# cinamin.net
KiCad netlist of a schematic drawn in EAGLE
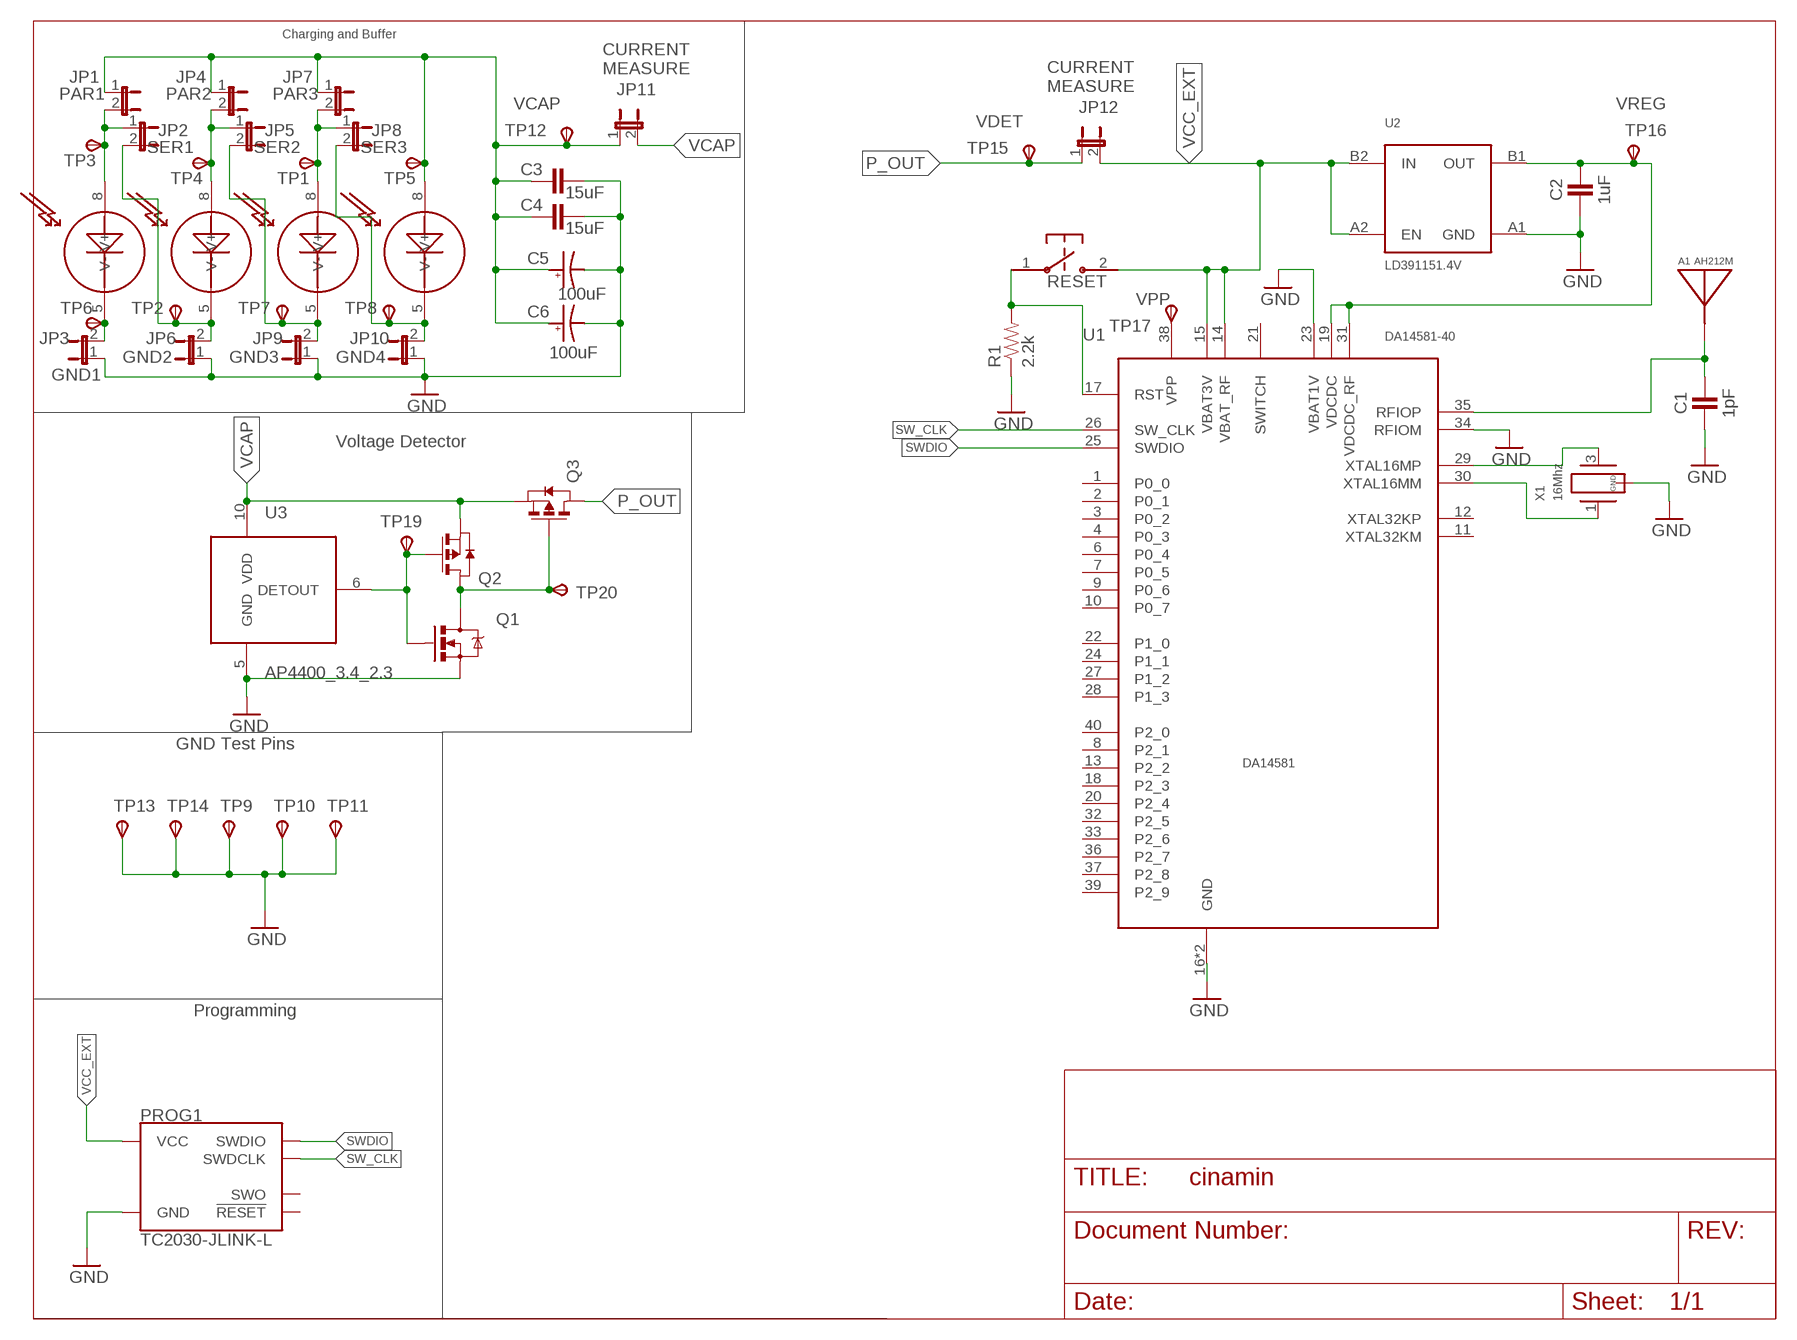
[diagram p0: schematic, sheet 1]

(export (version "E")
  (design (tool "Eeschema 10.0.6"))
  (components
    (comp (ref "A1")
      (value "AH212M")
      (footprint "eagle-import:AH212M")
      (libsource (lib "eagle-import") (part "AH212M"))
    )
    (comp (ref "C1")
      (value "1pF")
      (footprint "eagle-import:0402_CAP")
      (libsource (lib "eagle-import") (part "CAPACITOR"))
    )
    (comp (ref "C2")
      (value "1uF")
      (footprint "eagle-import:0402_CAP")
      (libsource (lib "eagle-import") (part "CAPACITOR"))
    )
    (comp (ref "C3")
      (value "15uF")
      (footprint "eagle-import:0402_CAP")
      (libsource (lib "eagle-import") (part "CAPACITOR"))
    )
    (comp (ref "C4")
      (value "15uF")
      (footprint "eagle-import:0402_CAP")
      (libsource (lib "eagle-import") (part "CAPACITOR"))
    )
    (comp (ref "C5")
      (value "100uF")
      (footprint "eagle-import:CAP0603")
      (libsource (lib "eagle-import") (part "CAP_POL0603"))
    )
    (comp (ref "C6")
      (value "100uF")
      (footprint "eagle-import:CAP0603")
      (libsource (lib "eagle-import") (part "CAP_POL0603"))
    )
    (comp (ref "D1")
      (value "CPC1822")
      (footprint "eagle-import:SOIC-8")
      (libsource (lib "eagle-import") (part "CPC1822"))
    )
    (comp (ref "D2")
      (value "CPC1822")
      (footprint "eagle-import:SOIC-8")
      (libsource (lib "eagle-import") (part "CPC1822"))
    )
    (comp (ref "D3")
      (value "CPC1822")
      (footprint "eagle-import:SOIC-8")
      (libsource (lib "eagle-import") (part "CPC1822"))
    )
    (comp (ref "D4")
      (value "CPC1822")
      (footprint "eagle-import:SOIC-8")
      (libsource (lib "eagle-import") (part "CPC1822"))
    )
    (comp (ref "JP1")
      (value "PAR1")
      (footprint "eagle-import:1X02")
      (libsource (lib "eagle-import") (part "JUMPER-2PTH"))
    )
    (comp (ref "JP2")
      (value "SER1")
      (footprint "eagle-import:1X02")
      (libsource (lib "eagle-import") (part "JUMPER-2PTH"))
    )
    (comp (ref "JP3")
      (value "GND1")
      (footprint "eagle-import:1X02")
      (libsource (lib "eagle-import") (part "JUMPER-2PTH"))
    )
    (comp (ref "JP4")
      (value "PAR2")
      (footprint "eagle-import:1X02")
      (libsource (lib "eagle-import") (part "JUMPER-2PTH"))
    )
    (comp (ref "JP5")
      (value "SER2")
      (footprint "eagle-import:1X02")
      (libsource (lib "eagle-import") (part "JUMPER-2PTH"))
    )
    (comp (ref "JP6")
      (value "GND2")
      (footprint "eagle-import:1X02")
      (libsource (lib "eagle-import") (part "JUMPER-2PTH"))
    )
    (comp (ref "JP7")
      (value "PAR3")
      (footprint "eagle-import:1X02")
      (libsource (lib "eagle-import") (part "JUMPER-2PTH"))
    )
    (comp (ref "JP8")
      (value "SER3")
      (footprint "eagle-import:1X02")
      (libsource (lib "eagle-import") (part "JUMPER-2PTH"))
    )
    (comp (ref "JP9")
      (value "GND3")
      (footprint "eagle-import:1X02")
      (libsource (lib "eagle-import") (part "JUMPER-2PTH"))
    )
    (comp (ref "JP10")
      (value "GND4")
      (footprint "eagle-import:1X02")
      (libsource (lib "eagle-import") (part "JUMPER-2PTH"))
    )
    (comp (ref "JP11")
      (value "CURRENT_MEASURE1")
      (footprint "eagle-import:1X02")
      (libsource (lib "eagle-import") (part "JUMPER-2PTH"))
    )
    (comp (ref "JP12")
      (value "CURRENT_MEASURE2")
      (footprint "eagle-import:1X02")
      (libsource (lib "eagle-import") (part "JUMPER-2PTH"))
    )
    (comp (ref "PROG1")
      (value "TC2030-JLINK-L")
      (footprint "eagle-import:TC2030-IDC")
      (libsource (lib "eagle-import") (part "TC2030-JLINK-L"))
    )
    (comp (ref "Q1")
      (value "MOSFET-NCHANNELXFDN-3")
      (footprint "eagle-import:XFDFN-3")
      (libsource (lib "eagle-import") (part "MOSFET-NCHANNELXFDN-3"))
    )
    (comp (ref "Q2")
      (value "MOSFET-PCHANNEL")
      (footprint "eagle-import:XFDFN-3")
      (libsource (lib "eagle-import") (part "MOSFET-PCHANNEL"))
    )
    (comp (ref "Q3")
      (value "MOSFET-PCHANNEL")
      (footprint "eagle-import:XFDFN-3")
      (libsource (lib "eagle-import") (part "MOSFET-PCHANNEL"))
    )
    (comp (ref "R1")
      (value "2.2k")
      (footprint "eagle-import:0402_RES")
      (libsource (lib "eagle-import") (part "RESISTOR0402_RES"))
    )
    (comp (ref "RESET")
      (value "B3U-1000P")
      (footprint "eagle-import:B3U-1000P")
      (libsource (lib "eagle-import") (part "B3U-1000P"))
    )
    (comp (ref "TP1")
      (value "D3H")
      (footprint "eagle-import:P1-13")
      (libsource (lib "eagle-import") (part "TPSPAD1-13"))
    )
    (comp (ref "TP2")
      (value "D2L")
      (footprint "eagle-import:P1-13")
      (libsource (lib "eagle-import") (part "TPSPAD1-13"))
    )
    (comp (ref "TP3")
      (value "D1H")
      (footprint "eagle-import:P1-13")
      (libsource (lib "eagle-import") (part "TPSPAD1-13"))
    )
    (comp (ref "TP4")
      (value "D2H")
      (footprint "eagle-import:P1-13")
      (libsource (lib "eagle-import") (part "TPSPAD1-13"))
    )
    (comp (ref "TP5")
      (value "D4H")
      (footprint "eagle-import:P1-13")
      (libsource (lib "eagle-import") (part "TPSPAD1-13"))
    )
    (comp (ref "TP6")
      (value "D1L")
      (footprint "eagle-import:P1-13")
      (libsource (lib "eagle-import") (part "TPSPAD1-13"))
    )
    (comp (ref "TP7")
      (value "D3L")
      (footprint "eagle-import:P1-13")
      (libsource (lib "eagle-import") (part "TPSPAD1-13"))
    )
    (comp (ref "TP8")
      (value "D4L")
      (footprint "eagle-import:P1-13")
      (libsource (lib "eagle-import") (part "TPSPAD1-13"))
    )
    (comp (ref "TP9")
      (value "GND")
      (footprint "eagle-import:P1-13")
      (libsource (lib "eagle-import") (part "TPSPAD1-13"))
    )
    (comp (ref "TP10")
      (value "GND")
      (footprint "eagle-import:P1-13")
      (libsource (lib "eagle-import") (part "TPSPAD1-13"))
    )
    (comp (ref "TP11")
      (value "GND")
      (footprint "eagle-import:P1-13")
      (libsource (lib "eagle-import") (part "TPSPAD1-13"))
    )
    (comp (ref "TP12")
      (value "VCAP")
      (footprint "eagle-import:P1-13")
      (libsource (lib "eagle-import") (part "TPSPAD1-13"))
    )
    (comp (ref "TP13")
      (value "GND")
      (footprint "eagle-import:P1-13")
      (libsource (lib "eagle-import") (part "TPSPAD1-13"))
    )
    (comp (ref "TP14")
      (value "GND")
      (footprint "eagle-import:P1-13")
      (libsource (lib "eagle-import") (part "TPSPAD1-13"))
    )
    (comp (ref "TP15")
      (value "VDET")
      (footprint "eagle-import:P1-13")
      (libsource (lib "eagle-import") (part "TPSPAD1-13"))
    )
    (comp (ref "TP16")
      (value "VREG")
      (footprint "eagle-import:P1-13")
      (libsource (lib "eagle-import") (part "TPSPAD1-13"))
    )
    (comp (ref "TP17")
      (value "VPP")
      (footprint "eagle-import:P1-13")
      (libsource (lib "eagle-import") (part "TPSPAD1-13"))
    )
    (comp (ref "TP19")
      (value "VCAP")
      (footprint "eagle-import:P1-13")
      (libsource (lib "eagle-import") (part "TPSPAD1-13"))
    )
    (comp (ref "TP20")
      (value "VCAP")
      (footprint "eagle-import:P1-13")
      (libsource (lib "eagle-import") (part "TPSPAD1-13"))
    )
    (comp (ref "U1")
      (value "DA14581-40")
      (footprint "eagle-import:QFN-40-5MM")
      (libsource (lib "eagle-import") (part "DA14581-40"))
    )
    (comp (ref "U2")
      (value "LD391151.4V")
      (footprint "eagle-import:FLIP_CHIP-4")
      (libsource (lib "eagle-import") (part "LD391151.4V"))
    )
    (comp (ref "U3")
      (value "AP4400_3.4_2.3")
      (footprint "eagle-import:TSOP-10")
      (libsource (lib "eagle-import") (part "AP4400"))
    )
    (comp (ref "X1")
      (value "16Mhz")
      (footprint "eagle-import:TXC-8Y")
      (libsource (lib "eagle-import") (part "TXC-8Y"))
    )
  )
  (nets
    (net (code "1") (name "GND") (class "Default")
      (node (ref "C1") (pin "2") (pinfunction "2_2") (pintype "bidirectional"))
      (node (ref "C2") (pin "2") (pinfunction "2_2") (pintype "bidirectional"))
      (node (ref "C3") (pin "2") (pinfunction "2_2") (pintype "bidirectional"))
      (node (ref "C4") (pin "2") (pinfunction "2_2") (pintype "bidirectional"))
      (node (ref "C5") (pin "NEG") (pinfunction "ANODE_NEG") (pintype "bidirectional"))
      (node (ref "C6") (pin "NEG") (pinfunction "ANODE_NEG") (pintype "bidirectional"))
      (node (ref "JP10") (pin "1") (pinfunction "1_1") (pintype "passive"))
      (node (ref "JP3") (pin "1") (pinfunction "1_1") (pintype "passive"))
      (node (ref "JP6") (pin "1") (pinfunction "1_1") (pintype "passive"))
      (node (ref "JP9") (pin "1") (pinfunction "1_1") (pintype "passive"))
      (node (ref "PROG1") (pin "5") (pinfunction "GND_5") (pintype "bidirectional"))
      (node (ref "Q1") (pin "S") (pinfunction "S_S") (pintype "passive"))
      (node (ref "R1") (pin "1") (pinfunction "1_1") (pintype "passive"))
      (node (ref "TP10") (pin "TP") (pinfunction "PP_TP") (pintype "input"))
      (node (ref "TP11") (pin "TP") (pinfunction "PP_TP") (pintype "input"))
      (node (ref "TP13") (pin "TP") (pinfunction "PP_TP") (pintype "input"))
      (node (ref "TP14") (pin "TP") (pinfunction "PP_TP") (pintype "input"))
      (node (ref "TP9") (pin "TP") (pinfunction "PP_TP") (pintype "input"))
      (node (ref "U1") (pin "16") (pinfunction "GND_16") (pintype "bidirectional"))
      (node (ref "U1") (pin "23") (pinfunction "VBAT1V_23") (pintype "bidirectional"))
      (node (ref "U1") (pin "34") (pinfunction "RFIOM_34") (pintype "bidirectional"))
      (node (ref "U1") (pin "PAD") (pinfunction "GND_PAD") (pintype "bidirectional"))
      (node (ref "U2") (pin "A1") (pinfunction "GND_A1") (pintype "bidirectional"))
      (node (ref "U3") (pin "5") (pinfunction "GND_5") (pintype "bidirectional"))
      (node (ref "X1") (pin "2") (pinfunction "GND_2") (pintype "bidirectional"))
      (node (ref "X1") (pin "4") (pinfunction "GND_4") (pintype "bidirectional"))
    )
    (net (code "2") (name "Net-(A1-ANTENNA)") (class "Default")
      (node (ref "A1") (pin "P1") (pinfunction "ANTENNA_P1") (pintype "bidirectional"))
      (node (ref "C1") (pin "1") (pinfunction "1_1") (pintype "bidirectional"))
      (node (ref "U1") (pin "35") (pinfunction "RFIOP_35") (pintype "bidirectional"))
    )
    (net (code "3") (name "Net-(C5-CATHODE)") (class "Default")
      (node (ref "C3") (pin "1") (pinfunction "1_1") (pintype "bidirectional"))
      (node (ref "C4") (pin "1") (pinfunction "1_1") (pintype "bidirectional"))
      (node (ref "C5") (pin "POS") (pinfunction "CATHODE_POS") (pintype "bidirectional"))
      (node (ref "C6") (pin "POS") (pinfunction "CATHODE_POS") (pintype "bidirectional"))
      (node (ref "D4") (pin "8") (pinfunction "V+_8") (pintype "bidirectional"))
      (node (ref "JP1") (pin "1") (pinfunction "1_1") (pintype "passive"))
      (node (ref "JP11") (pin "1") (pinfunction "1_1") (pintype "passive"))
      (node (ref "JP4") (pin "1") (pinfunction "1_1") (pintype "passive"))
      (node (ref "JP7") (pin "1") (pinfunction "1_1") (pintype "passive"))
      (node (ref "TP12") (pin "TP") (pinfunction "PP_TP") (pintype "input"))
      (node (ref "TP5") (pin "TP") (pinfunction "PP_TP") (pintype "input"))
    )
    (net (code "4") (name "Net-(D1-V+)") (class "Default")
      (node (ref "D1") (pin "8") (pinfunction "V+_8") (pintype "bidirectional"))
      (node (ref "JP1") (pin "2") (pinfunction "2_2") (pintype "passive"))
      (node (ref "JP2") (pin "1") (pinfunction "1_1") (pintype "passive"))
      (node (ref "TP3") (pin "TP") (pinfunction "PP_TP") (pintype "input"))
    )
    (net (code "5") (name "Net-(D1-V-)") (class "Default")
      (node (ref "D1") (pin "5") (pinfunction "V-_5") (pintype "bidirectional"))
      (node (ref "JP3") (pin "2") (pinfunction "2_2") (pintype "passive"))
      (node (ref "TP6") (pin "TP") (pinfunction "PP_TP") (pintype "input"))
    )
    (net (code "6") (name "Net-(D2-V+)") (class "Default")
      (node (ref "D2") (pin "8") (pinfunction "V+_8") (pintype "bidirectional"))
      (node (ref "JP4") (pin "2") (pinfunction "2_2") (pintype "passive"))
      (node (ref "JP5") (pin "1") (pinfunction "1_1") (pintype "passive"))
      (node (ref "TP4") (pin "TP") (pinfunction "PP_TP") (pintype "input"))
    )
    (net (code "7") (name "Net-(D2-V-)") (class "Default")
      (node (ref "D2") (pin "5") (pinfunction "V-_5") (pintype "bidirectional"))
      (node (ref "JP2") (pin "2") (pinfunction "2_2") (pintype "passive"))
      (node (ref "JP6") (pin "2") (pinfunction "2_2") (pintype "passive"))
      (node (ref "TP2") (pin "TP") (pinfunction "PP_TP") (pintype "input"))
    )
    (net (code "8") (name "Net-(D3-V+)") (class "Default")
      (node (ref "D3") (pin "8") (pinfunction "V+_8") (pintype "bidirectional"))
      (node (ref "JP7") (pin "2") (pinfunction "2_2") (pintype "passive"))
      (node (ref "JP8") (pin "1") (pinfunction "1_1") (pintype "passive"))
      (node (ref "TP1") (pin "TP") (pinfunction "PP_TP") (pintype "input"))
    )
    (net (code "9") (name "Net-(D3-V-)") (class "Default")
      (node (ref "D3") (pin "5") (pinfunction "V-_5") (pintype "bidirectional"))
      (node (ref "JP5") (pin "2") (pinfunction "2_2") (pintype "passive"))
      (node (ref "JP9") (pin "2") (pinfunction "2_2") (pintype "passive"))
      (node (ref "TP7") (pin "TP") (pinfunction "PP_TP") (pintype "input"))
    )
    (net (code "10") (name "Net-(D4-V-)") (class "Default")
      (node (ref "D4") (pin "5") (pinfunction "V-_5") (pintype "bidirectional"))
      (node (ref "JP10") (pin "2") (pinfunction "2_2") (pintype "passive"))
      (node (ref "JP8") (pin "2") (pinfunction "2_2") (pintype "passive"))
      (node (ref "TP8") (pin "TP") (pinfunction "PP_TP") (pintype "input"))
    )
    (net (code "11") (name "Net-(RESET-P$1)") (class "Default")
      (node (ref "R1") (pin "2") (pinfunction "2_2") (pintype "passive"))
      (node (ref "RESET") (pin "1") (pinfunction "P$1_1") (pintype "passive"))
      (node (ref "U1") (pin "17") (pinfunction "RST_17") (pintype "bidirectional"))
    )
    (net (code "12") (name "Net-(TP16-PP)") (class "Default")
      (node (ref "C2") (pin "1") (pinfunction "1_1") (pintype "bidirectional"))
      (node (ref "TP16") (pin "TP") (pinfunction "PP_TP") (pintype "input"))
      (node (ref "U1") (pin "19") (pinfunction "VDCDC_19") (pintype "bidirectional"))
      (node (ref "U1") (pin "31") (pinfunction "VDCDC_RF_31") (pintype "bidirectional"))
      (node (ref "U2") (pin "B1") (pinfunction "OUT_B1") (pintype "bidirectional"))
    )
    (net (code "13") (name "Net-(TP17-PP)") (class "Default")
      (node (ref "TP17") (pin "TP") (pinfunction "PP_TP") (pintype "input"))
      (node (ref "U1") (pin "38") (pinfunction "VPP_38") (pintype "bidirectional"))
    )
    (net (code "14") (name "Net-(TP19-PP)") (class "Default")
      (node (ref "Q1") (pin "G") (pinfunction "G_G") (pintype "passive"))
      (node (ref "Q2") (pin "G") (pinfunction "G_G") (pintype "passive"))
      (node (ref "TP19") (pin "TP") (pinfunction "PP_TP") (pintype "input"))
      (node (ref "U3") (pin "6") (pinfunction "DETOUT_6") (pintype "bidirectional"))
    )
    (net (code "15") (name "Net-(TP20-PP)") (class "Default")
      (node (ref "Q1") (pin "D") (pinfunction "D_D") (pintype "passive"))
      (node (ref "Q2") (pin "D") (pinfunction "D_D") (pintype "passive"))
      (node (ref "Q3") (pin "G") (pinfunction "G_G") (pintype "passive"))
      (node (ref "TP20") (pin "TP") (pinfunction "PP_TP") (pintype "input"))
    )
    (net (code "16") (name "Net-(U1-XTAL16MM)") (class "Default")
      (node (ref "U1") (pin "30") (pinfunction "XTAL16MM_30") (pintype "bidirectional"))
      (node (ref "X1") (pin "1") (pinfunction "1_1") (pintype "bidirectional"))
    )
    (net (code "17") (name "Net-(U1-XTAL16MP)") (class "Default")
      (node (ref "U1") (pin "29") (pinfunction "XTAL16MP_29") (pintype "bidirectional"))
      (node (ref "X1") (pin "3") (pinfunction "2_3") (pintype "bidirectional"))
    )
    (net (code "18") (name "P_OUT") (class "Default")
      (node (ref "JP12") (pin "1") (pinfunction "1_1") (pintype "passive"))
      (node (ref "Q3") (pin "D") (pinfunction "D_D") (pintype "passive"))
      (node (ref "TP15") (pin "TP") (pinfunction "PP_TP") (pintype "input"))
    )
    (net (code "19") (name "SWDIO") (class "Default")
      (node (ref "PROG1") (pin "2") (pinfunction "SWDIO_2") (pintype "bidirectional"))
      (node (ref "U1") (pin "25") (pinfunction "SWDIO_25") (pintype "bidirectional"))
    )
    (net (code "20") (name "SW_CLK") (class "Default")
      (node (ref "PROG1") (pin "4") (pinfunction "SWDCLK_4") (pintype "bidirectional"))
      (node (ref "U1") (pin "26") (pinfunction "SW_CLK_26") (pintype "bidirectional"))
    )
    (net (code "21") (name "VCAP") (class "Default")
      (node (ref "JP11") (pin "2") (pinfunction "2_2") (pintype "passive"))
      (node (ref "Q2") (pin "S") (pinfunction "S_S") (pintype "passive"))
      (node (ref "Q3") (pin "S") (pinfunction "S_S") (pintype "passive"))
      (node (ref "U3") (pin "10") (pinfunction "VDD_10") (pintype "bidirectional"))
    )
    (net (code "22") (name "VCC_EXT") (class "Default")
      (node (ref "JP12") (pin "2") (pinfunction "2_2") (pintype "passive"))
      (node (ref "PROG1") (pin "1") (pinfunction "VCC_1") (pintype "bidirectional"))
      (node (ref "RESET") (pin "2") (pinfunction "P$2_2") (pintype "passive"))
      (node (ref "U1") (pin "14") (pinfunction "VBAT_RF_14") (pintype "bidirectional"))
      (node (ref "U1") (pin "15") (pinfunction "VBAT3V_15") (pintype "bidirectional"))
      (node (ref "U2") (pin "A2") (pinfunction "EN_A2") (pintype "bidirectional"))
      (node (ref "U2") (pin "B2") (pinfunction "IN_B2") (pintype "bidirectional"))
    )
    (net (code "23") (name "unconnected-(PROG1-SWO-Pad6)") (class "Default")
      (node (ref "PROG1") (pin "6") (pinfunction "SWO_6") (pintype "bidirectional"))
    )
    (net (code "24") (name "unconnected-(PROG1-~{RESET}-Pad3)") (class "Default")
      (node (ref "PROG1") (pin "3") (pinfunction "~{RESET}_3") (pintype "bidirectional"))
    )
    (net (code "25") (name "unconnected-(U1-P0_0-Pad1)") (class "Default")
      (node (ref "U1") (pin "1") (pinfunction "P0_0_1") (pintype "bidirectional"))
    )
    (net (code "26") (name "unconnected-(U1-P0_1-Pad2)") (class "Default")
      (node (ref "U1") (pin "2") (pinfunction "P0_1_2") (pintype "bidirectional"))
    )
    (net (code "27") (name "unconnected-(U1-P0_2-Pad3)") (class "Default")
      (node (ref "U1") (pin "3") (pinfunction "P0_2_3") (pintype "bidirectional"))
    )
    (net (code "28") (name "unconnected-(U1-P0_3-Pad4)") (class "Default")
      (node (ref "U1") (pin "4") (pinfunction "P0_3_4") (pintype "bidirectional"))
    )
    (net (code "29") (name "unconnected-(U1-P0_4-Pad6)") (class "Default")
      (node (ref "U1") (pin "6") (pinfunction "P0_4_6") (pintype "bidirectional"))
    )
    (net (code "30") (name "unconnected-(U1-P0_5-Pad7)") (class "Default")
      (node (ref "U1") (pin "7") (pinfunction "P0_5_7") (pintype "bidirectional"))
    )
    (net (code "31") (name "unconnected-(U1-P0_6-Pad9)") (class "Default")
      (node (ref "U1") (pin "9") (pinfunction "P0_6_9") (pintype "bidirectional"))
    )
    (net (code "32") (name "unconnected-(U1-P0_7-Pad10)") (class "Default")
      (node (ref "U1") (pin "10") (pinfunction "P0_7_10") (pintype "bidirectional"))
    )
    (net (code "33") (name "unconnected-(U1-P1_0-Pad22)") (class "Default")
      (node (ref "U1") (pin "22") (pinfunction "P1_0_22") (pintype "bidirectional"))
    )
    (net (code "34") (name "unconnected-(U1-P1_1-Pad24)") (class "Default")
      (node (ref "U1") (pin "24") (pinfunction "P1_1_24") (pintype "bidirectional"))
    )
    (net (code "35") (name "unconnected-(U1-P1_2-Pad27)") (class "Default")
      (node (ref "U1") (pin "27") (pinfunction "P1_2_27") (pintype "bidirectional"))
    )
    (net (code "36") (name "unconnected-(U1-P1_3-Pad28)") (class "Default")
      (node (ref "U1") (pin "28") (pinfunction "P1_3_28") (pintype "bidirectional"))
    )
    (net (code "37") (name "unconnected-(U1-P2_0-Pad40)") (class "Default")
      (node (ref "U1") (pin "40") (pinfunction "P2_0_40") (pintype "bidirectional"))
    )
    (net (code "38") (name "unconnected-(U1-P2_1-Pad8)") (class "Default")
      (node (ref "U1") (pin "8") (pinfunction "P2_1_8") (pintype "bidirectional"))
    )
    (net (code "39") (name "unconnected-(U1-P2_2-Pad13)") (class "Default")
      (node (ref "U1") (pin "13") (pinfunction "P2_2_13") (pintype "bidirectional"))
    )
    (net (code "40") (name "unconnected-(U1-P2_3-Pad18)") (class "Default")
      (node (ref "U1") (pin "18") (pinfunction "P2_3_18") (pintype "bidirectional"))
    )
    (net (code "41") (name "unconnected-(U1-P2_4-Pad20)") (class "Default")
      (node (ref "U1") (pin "20") (pinfunction "P2_4_20") (pintype "bidirectional"))
    )
    (net (code "42") (name "unconnected-(U1-P2_5-Pad32)") (class "Default")
      (node (ref "U1") (pin "32") (pinfunction "P2_5_32") (pintype "bidirectional"))
    )
    (net (code "43") (name "unconnected-(U1-P2_6-Pad33)") (class "Default")
      (node (ref "U1") (pin "33") (pinfunction "P2_6_33") (pintype "bidirectional"))
    )
    (net (code "44") (name "unconnected-(U1-P2_7-Pad36)") (class "Default")
      (node (ref "U1") (pin "36") (pinfunction "P2_7_36") (pintype "bidirectional"))
    )
    (net (code "45") (name "unconnected-(U1-P2_8-Pad37)") (class "Default")
      (node (ref "U1") (pin "37") (pinfunction "P2_8_37") (pintype "bidirectional"))
    )
    (net (code "46") (name "unconnected-(U1-P2_9-Pad39)") (class "Default")
      (node (ref "U1") (pin "39") (pinfunction "P2_9_39") (pintype "bidirectional"))
    )
    (net (code "47") (name "unconnected-(U1-SWITCH-Pad21)") (class "Default")
      (node (ref "U1") (pin "21") (pinfunction "SWITCH_21") (pintype "bidirectional"))
    )
    (net (code "48") (name "unconnected-(U1-XTAL32KM-Pad11)") (class "Default")
      (node (ref "U1") (pin "11") (pinfunction "XTAL32KM_11") (pintype "bidirectional"))
    )
    (net (code "49") (name "unconnected-(U1-XTAL32KP-Pad12)") (class "Default")
      (node (ref "U1") (pin "12") (pinfunction "XTAL32KP_12") (pintype "bidirectional"))
    )
  )
)
